# uC.net
KiCad netlist of a schematic drawn in Altium Designer
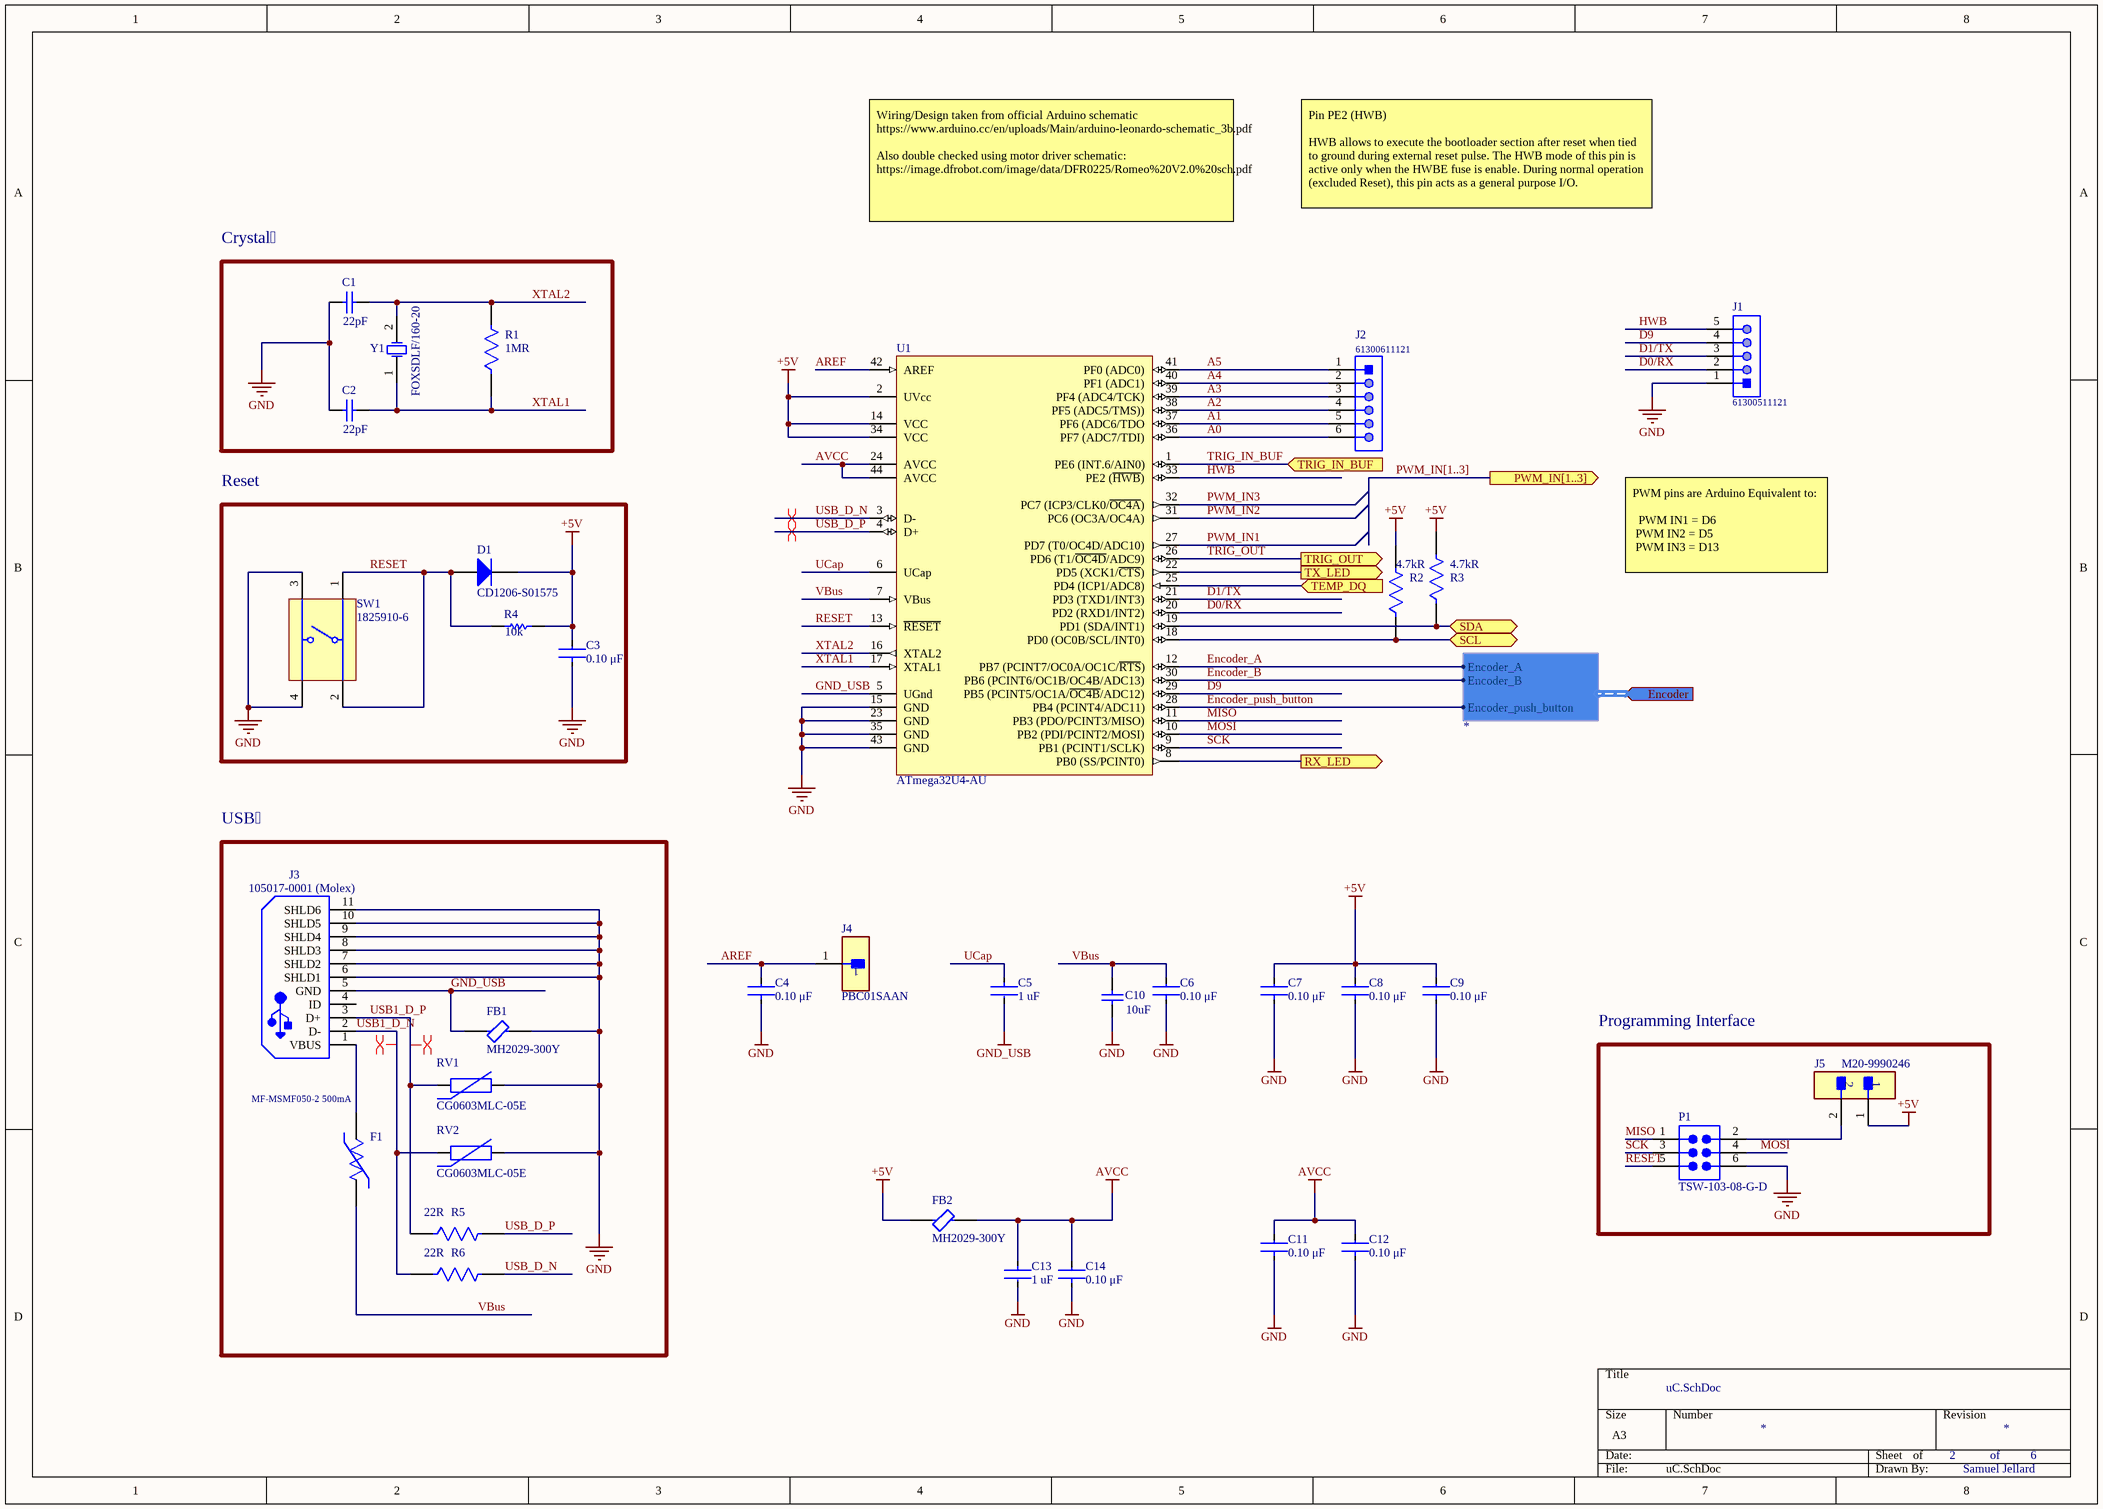
[diagram p0: uC.SchDoc]

(export (version "E")
  (design (tool "Eeschema 10.0.6"))
  (components
    (comp (ref "C1")
      (value "CC0603JRNPO9BN220")
      (footprint "CAPC1608X90X40LL10T20")
      (description "Chip Capacitor, 22 pF, +/- 5%, 50 V, -55 to 125 degC, 0603 (1608 Metric), RoHS, Tape and Reel")
      (libsource (lib "Altium Content Vault") (part "CAP-NP-2"))
    )
    (comp (ref "C2")
      (value "CC0603JRNPO9BN220")
      (footprint "CAPC1608X90X40LL10T20")
      (description "Chip Capacitor, 22 pF, +/- 5%, 50 V, -55 to 125 degC, 0603 (1608 Metric), RoHS, Tape and Reel")
      (libsource (lib "Altium Content Vault") (part "CAP-NP-2"))
    )
    (comp (ref "C3")
      (value "0.10 μF")
      (footprint "FP-C0603C-CF-MFG")
      (description "Multilayer Ceramic Capacitors (MLCC) - SMD/SMT 50volts 0.1uF X7R 10%")
      (fields (field (name "TOLERANCE") "0.1") (field (name "MANUFACTURER") "KEMET"))
      (libsource (lib "Altium Content Vault") (part "b4654b650e69147ec39a6b967a45e02"))
    )
    (comp (ref "C4")
      (value "0.10 μF")
      (footprint "FP-C0603C-CF-MFG")
      (description "Multilayer Ceramic Capacitors (MLCC) - SMD/SMT 50volts 0.1uF X7R 10%")
      (fields (field (name "TOLERANCE") "0.1") (field (name "MANUFACTURER") "KEMET"))
      (libsource (lib "Altium Content Vault") (part "b4654b650e69147ec39a6b967a45e02"))
    )
    (comp (ref "C5")
      (value "1 uF")
      (footprint "FP-CC0603-DA-MFG")
      (description "0603 1 uF 16 V ±10 % Tolerance X7R SMT Multilayer Ceramic Capacitor")
      (fields (field (name "TOLERANCE") "0.1") (field (name "MANUFACTURER") "YAGEO"))
      (libsource (lib "Altium Content Vault") (part "11868f565c42a9108669ba33697ecf6"))
    )
    (comp (ref "C6")
      (value "0.10 μF")
      (footprint "FP-C0603C-CF-MFG")
      (description "Multilayer Ceramic Capacitors (MLCC) - SMD/SMT 50volts 0.1uF X7R 10%")
      (fields (field (name "TOLERANCE") "0.1") (field (name "MANUFACTURER") "KEMET"))
      (libsource (lib "Altium Content Vault") (part "b4654b650e69147ec39a6b967a45e02"))
    )
    (comp (ref "C7")
      (value "0.10 μF")
      (footprint "FP-C0603C-CF-MFG")
      (description "Multilayer Ceramic Capacitors (MLCC) - SMD/SMT 50volts 0.1uF X7R 10%")
      (fields (field (name "TOLERANCE") "0.1") (field (name "MANUFACTURER") "KEMET"))
      (libsource (lib "Altium Content Vault") (part "b4654b650e69147ec39a6b967a45e02"))
    )
    (comp (ref "C8")
      (value "0.10 μF")
      (footprint "FP-C0603C-CF-MFG")
      (description "Multilayer Ceramic Capacitors (MLCC) - SMD/SMT 50volts 0.1uF X7R 10%")
      (fields (field (name "TOLERANCE") "0.1") (field (name "MANUFACTURER") "KEMET"))
      (libsource (lib "Altium Content Vault") (part "b4654b650e69147ec39a6b967a45e02"))
    )
    (comp (ref "C9")
      (value "0.10 μF")
      (footprint "FP-C0603C-CF-MFG")
      (description "Multilayer Ceramic Capacitors (MLCC) - SMD/SMT 50volts 0.1uF X7R 10%")
      (fields (field (name "TOLERANCE") "0.1") (field (name "MANUFACTURER") "KEMET"))
      (libsource (lib "Altium Content Vault") (part "b4654b650e69147ec39a6b967a45e02"))
    )
    (comp (ref "C10")
      (value "10uF")
      (footprint "CAPC0603(1608)100_N")
      (description "CAP 10uF 6.3V ±20% 0603 (1608 Metric) Thickness 1mm SMD")
      (fields (field (name "TOLERANCE") "Â±20%") (field (name "Comment") "C0603C106M9PACTU"))
      (libsource (lib "Altium Content Vault") (part "CAP"))
    )
    (comp (ref "C11")
      (value "0.10 μF")
      (footprint "FP-C0603C-CF-MFG")
      (description "Multilayer Ceramic Capacitors (MLCC) - SMD/SMT 50volts 0.1uF X7R 10%")
      (fields (field (name "TOLERANCE") "0.1") (field (name "MANUFACTURER") "KEMET"))
      (libsource (lib "Altium Content Vault") (part "b4654b650e69147ec39a6b967a45e02"))
    )
    (comp (ref "C12")
      (value "0.10 μF")
      (footprint "FP-C0603C-CF-MFG")
      (description "Multilayer Ceramic Capacitors (MLCC) - SMD/SMT 50volts 0.1uF X7R 10%")
      (fields (field (name "TOLERANCE") "0.1") (field (name "MANUFACTURER") "KEMET"))
      (libsource (lib "Altium Content Vault") (part "b4654b650e69147ec39a6b967a45e02"))
    )
    (comp (ref "C13")
      (value "1 uF")
      (footprint "FP-CC0603-DA-MFG")
      (description "0603 1 uF 16 V ±10 % Tolerance X7R SMT Multilayer Ceramic Capacitor")
      (fields (field (name "TOLERANCE") "0.1") (field (name "MANUFACTURER") "YAGEO"))
      (libsource (lib "Altium Content Vault") (part "11868f565c42a9108669ba33697ecf6"))
    )
    (comp (ref "C14")
      (value "0.10 μF")
      (footprint "FP-C0603C-CF-MFG")
      (description "Multilayer Ceramic Capacitors (MLCC) - SMD/SMT 50volts 0.1uF X7R 10%")
      (fields (field (name "TOLERANCE") "0.1") (field (name "MANUFACTURER") "KEMET"))
      (libsource (lib "Altium Content Vault") (part "b4654b650e69147ec39a6b967a45e02"))
    )
    (comp (ref "D1")
      (value "CD1206-S01575")
      (footprint "BOUR-CD1206-S01575-2_L")
      (description "75 V Small Signal Switching Diode, 150 mA, 2.5 uA, 1026 Molded Package, RoHS, Tape and Reel")
      (fields (field (name "MANUFACTURER") "Bourns"))
      (libsource (lib "Altium Content Vault") (part "BOUR-A1K2-2"))
    )
    (comp (ref "F1")
      (value "MF-MSMF050-2 500mA")
      (footprint "FP-MF-MSMF050-2-MFG")
      (description "PTC RESET FUSE 15V 500MA 1812")
      (fields (field (name "MANUFACTURER") "Bourns") (field (name "MANUFACTURER PART NUMBER") "MF-MSMF050-2"))
      (libsource (lib "Altium Content Vault") (part "fc31388045fc42ab786d6d00b506e9f"))
    )
    (comp (ref "FB1")
      (value "MH2029-300Y")
      (footprint "FP-MH2029-MFG")
      (description "FERRITE BEAD 30 OHM 0805 1LN")
      (fields
        (field (name "OCTOPART") "https://octopart.com/mh2029-300y-bourns-756929")
        (field (name "MANUFACTURER") "Bourns")
      )
      (libsource (lib "Altium Content Vault") (part "5f30dd21d616792df468990f7003faa"))
    )
    (comp (ref "FB2")
      (value "MH2029-300Y")
      (footprint "FP-MH2029-MFG")
      (description "FERRITE BEAD 30 OHM 0805 1LN")
      (fields
        (field (name "OCTOPART") "https://octopart.com/mh2029-300y-bourns-756929")
        (field (name "MANUFACTURER") "Bourns")
      )
      (libsource (lib "Altium Content Vault") (part "5f30dd21d616792df468990f7003faa"))
    )
    (comp (ref "J1")
      (value "61300511121")
      (footprint "61300511121")
      (description "THT Vertical Pin Header WR-PHD, Pitch 2.54 mm, Single Row, 5 pins")
      (fields (field (name "MANUFACTURER") "Wurth Elektronik") (field (name "PUBLISHER") "WurthElektronik"))
      (libsource (lib "Altium Content Vault") (part "WE-CN-1P-M-R5"))
    )
    (comp (ref "J2")
      (value "61300611121")
      (footprint "61300611121")
      (description "THT Vertical Pin Header WR-PHD, Pitch 2.54 mm, Single Row, 6 pins")
      (fields (field (name "MANUFACTURER") "Wurth Elektronik") (field (name "PUBLISHER") "WurthElektronik"))
      (libsource (lib "Altium Content Vault") (part "WE-CN-1P-M-R6"))
    )
    (comp (ref "J3")
      (value "105017-0001 (Molex)")
      (footprint "USB-MICRO-B_V")
      (fields (field (name "MANUFACTURER") "Molex"))
      (libsource (lib "Altium Content Vault") (part "USB-5-6SHLD"))
    )
    (comp (ref "J4")
      (value "PBC01SAAN")
      (footprint "FP-PBC01SAAN-MFG")
      (description "CONN HEADER VERT 1POS")
      (libsource (lib "Altium Content Vault") (part "dd45045ce8184df9e99e12baf3f412c"))
    )
    (comp (ref "J5")
      (value "M20-9990246")
      (footprint "FP-M20-9990246-MFG")
      (description "2.54mm (0.1\") Pitch SIL Vertical PC Tail Pin Header, 6.1mm mating pin height, tin, 2 contacts")
      (fields
        (field (name "OCTOPART") "https://octopart.com/m20-9990246-harwin-2590635")
        (field (name "MANUFACTURER") "Harwin")
      )
      (libsource (lib "Altium Content Vault") (part "3bc925449376181038e59eaffc5286c"))
    )
    (comp (ref "P1")
      (value "TSW-103-08-G-D")
      (footprint "SMTC-TSW-103-08-X-D")
      (description "0.025\" SQ Post Header, Through-hole, Vertical, -55 to 125 degC, 2.54 mm Pitch, 6-Pin, Male, RoHS")
      (fields (field (name "MANUFACTURER") "Samtec"))
      (libsource (lib "Altium Content Vault") (part "SMTC-TSW-103-08-X-D"))
    )
    (comp (ref "R1")
      (value "CRCW06031M00FKEA")
      (footprint "FP-CRCW0603-e3-MFG")
      (description "RES Thick Film, 1MΩ, 1%, 0.1W, 100ppm/°C, 0603")
      (fields (field (name "RESISTANCE") "1MR") (field (name "TOLERANCE") "1%"))
      (libsource (lib "Altium Content Vault") (part "1029c3af85768c4190bb7ad29bc67b5"))
    )
    (comp (ref "R2")
      (value "CRCW06034K70FKEA")
      (footprint "FP-CRCW0603-e3-IPC_A")
      (description "RES Thick Film, 4.7kΩ, 1%, 0.1W, 100ppm/°C, 0603")
      (fields (field (name "RESISTANCE") "4.7kR") (field (name "TOLERANCE") "1%"))
      (libsource (lib "Altium Content Vault") (part "1029c3af85768c4190bb7ad29bc67b5"))
    )
    (comp (ref "R3")
      (value "CRCW06034K70FKEA")
      (footprint "FP-CRCW0603-e3-IPC_A")
      (description "RES Thick Film, 4.7kΩ, 1%, 0.1W, 100ppm/°C, 0603")
      (fields (field (name "RESISTANCE") "4.7kR") (field (name "TOLERANCE") "1%"))
      (libsource (lib "Altium Content Vault") (part "1029c3af85768c4190bb7ad29bc67b5"))
    )
    (comp (ref "R4")
      (value "CRCW060310K0FKEA")
      (footprint "RESC1609X50X30NL8T20")
      (description "Chip Resistor, 10 KOhm, +/- 1%, 100 mW, -55 to 155 degC, 0603 (1608 Metric), RoHS, Tape and Reel")
      (fields (field (name "MANUFACTURER") "Vishay Semiconductor"))
      (libsource (lib "Altium Content Vault") (part "RES-2"))
    )
    (comp (ref "R5")
      (value "CRCW060322R0FKEA")
      (footprint "FP-CRCW0603-e3-IPC_B")
      (description "RES Thick Film, 22Ω, 1%, 0.1W, 100ppm/°C, 0603")
      (fields (field (name "RESISTANCE") "22R") (field (name "TOLERANCE") "1%"))
      (libsource (lib "Altium Content Vault") (part "1029c3af85768c4190bb7ad29bc67b5"))
    )
    (comp (ref "R6")
      (value "CRCW060322R0FKEA")
      (footprint "FP-CRCW0603-e3-IPC_B")
      (description "RES Thick Film, 22Ω, 1%, 0.1W, 100ppm/°C, 0603")
      (fields (field (name "RESISTANCE") "22R") (field (name "TOLERANCE") "1%"))
      (libsource (lib "Altium Content Vault") (part "1029c3af85768c4190bb7ad29bc67b5"))
    )
    (comp (ref "RV1")
      (value "CG0603MLC-05E")
      (footprint "BOUR-CG0603-2_V")
      (description "ESD Protector, 5 V Supply, -40 to 85 degC, 1.6 x 0.8 x 0.55 mm SMD, RoHS, Tape and Reel")
      (fields (field (name "MANUFACTURER") "Bourns"))
      (libsource (lib "Altium Content Vault") (part "BOUR-VSR-2"))
    )
    (comp (ref "RV2")
      (value "CG0603MLC-05E")
      (footprint "BOUR-CG0603-2_V")
      (description "ESD Protector, 5 V Supply, -40 to 85 degC, 1.6 x 0.8 x 0.55 mm SMD, RoHS, Tape and Reel")
      (fields (field (name "MANUFACTURER") "Bourns"))
      (libsource (lib "Altium Content Vault") (part "BOUR-VSR-2"))
    )
    (comp (ref "SW1")
      (value "1825910-6")
      (footprint "TECO-1825910-6_V")
      (description "Tact Switch, SPST-NO, 0.05 A, -35 to 85 degC, 4-Pin THD, RoHS, Bulk")
      (fields (field (name "MANUFACTURER") "TE Connectivity"))
      (libsource (lib "Altium Content Vault") (part "SW-SPST-4_A"))
    )
    (comp (ref "U1")
      (value "ATmega32U4-AU")
      (footprint "44ML_M")
      (libsource (lib "Altium Content Vault") (part "MC-8B-ATM16U4-SQ44"))
    )
    (comp (ref "Y1")
      (value "FOXSDLF/160-20")
      (footprint "FOX-FOXSDLF160-20_V")
      (libsource (lib "Altium Content Vault") (part "XTAL_1-2-2"))
    )
  )
  (nets
    (net (code "2") (name "+5V") (class "Default")
      (node (ref "C3") (pin "2") (pinfunction "2_2") (pintype "passive"))
      (node (ref "C7") (pin "2") (pinfunction "2_2") (pintype "passive"))
      (node (ref "C8") (pin "2") (pinfunction "2_2") (pintype "passive"))
      (node (ref "C9") (pin "2") (pinfunction "2_2") (pintype "passive"))
      (node (ref "D1") (pin "2") (pinfunction "K_2") (pintype "passive"))
      (node (ref "FB2") (pin "2") (pinfunction "2_2") (pintype "passive"))
      (node (ref "J5") (pin "1") (pinfunction "1_1") (pintype "passive"))
      (node (ref "R2") (pin "2") (pinfunction "2_2") (pintype "passive"))
      (node (ref "R3") (pin "2") (pinfunction "2_2") (pintype "passive"))
      (node (ref "R4") (pin "2") (pinfunction "2_2") (pintype "passive"))
      (node (ref "U1") (pin "14") (pinfunction "VCC_14") (pintype "power_in"))
      (node (ref "U1") (pin "2") (pinfunction "UVcc_2") (pintype "power_in"))
      (node (ref "U1") (pin "34") (pinfunction "VCC_34") (pintype "power_in"))
    )
    (net (code "3") (name "/A0") (class "Default")
      (node (ref "J2") (pin "6") (pinfunction "6_6") (pintype "passive"))
      (node (ref "U1") (pin "36") (pinfunction "PF7_(ADC7/TDI)_36") (pintype "bidirectional"))
    )
    (net (code "4") (name "/A1") (class "Default")
      (node (ref "J2") (pin "5") (pinfunction "5_5") (pintype "passive"))
      (node (ref "U1") (pin "37") (pinfunction "PF6_(ADC6/TDO_37") (pintype "bidirectional"))
    )
    (net (code "5") (name "/A2") (class "Default")
      (node (ref "J2") (pin "4") (pinfunction "4_4") (pintype "passive"))
      (node (ref "U1") (pin "38") (pinfunction "PF5_(ADC5/TMS))_38") (pintype "bidirectional"))
    )
    (net (code "6") (name "/A3") (class "Default")
      (node (ref "J2") (pin "3") (pinfunction "3_3") (pintype "passive"))
      (node (ref "U1") (pin "39") (pinfunction "PF4_(ADC4/TCK)_39") (pintype "bidirectional"))
    )
    (net (code "7") (name "/A4") (class "Default")
      (node (ref "J2") (pin "2") (pinfunction "2_2") (pintype "passive"))
      (node (ref "U1") (pin "40") (pinfunction "PF1_(ADC1)_40") (pintype "bidirectional"))
    )
    (net (code "8") (name "/A5") (class "Default")
      (node (ref "J2") (pin "1") (pinfunction "1_1") (pintype "passive"))
      (node (ref "U1") (pin "41") (pinfunction "PF0_(ADC0)_41") (pintype "bidirectional"))
    )
    (net (code "9") (name "/AREF") (class "Default")
      (node (ref "C4") (pin "2") (pinfunction "2_2") (pintype "passive"))
      (node (ref "J4") (pin "1") (pinfunction "1_1") (pintype "passive"))
      (node (ref "U1") (pin "42") (pinfunction "AREF_42") (pintype "input"))
    )
    (net (code "10") (name "/D0{slash}RX") (class "Default")
      (node (ref "J1") (pin "2") (pinfunction "2_2") (pintype "passive"))
      (node (ref "U1") (pin "20") (pinfunction "PD2_(RXD1/INT2)_20") (pintype "bidirectional"))
    )
    (net (code "11") (name "/D1{slash}TX") (class "Default")
      (node (ref "J1") (pin "3") (pinfunction "3_3") (pintype "passive"))
      (node (ref "U1") (pin "21") (pinfunction "PD3_(TXD1/INT3)_21") (pintype "bidirectional"))
    )
    (net (code "12") (name "/D9") (class "Default")
      (node (ref "J1") (pin "4") (pinfunction "4_4") (pintype "passive"))
      (node (ref "U1") (pin "29") (pinfunction "PB5_(PCINT5/OC1A/~{OC4B}/ADC12)_29") (pintype "bidirectional"))
    )
    (net (code "13") (name "/Encoder_A") (class "Default")
      (node (ref "U1") (pin "12") (pinfunction "PB7_(PCINT7/OC0A/OC1C/~{RTS})_12") (pintype "bidirectional"))
    )
    (net (code "14") (name "/Encoder_B") (class "Default")
      (node (ref "U1") (pin "30") (pinfunction "PB6_(PCINT6/OC1B/OC4B/ADC13)_30") (pintype "bidirectional"))
    )
    (net (code "15") (name "/Encoder_push_button") (class "Default")
      (node (ref "U1") (pin "28") (pinfunction "PB4_(PCINT4/ADC11)_28") (pintype "bidirectional"))
    )
    (net (code "16") (name "/HWB") (class "Default")
      (node (ref "J1") (pin "5") (pinfunction "5_5") (pintype "passive"))
      (node (ref "U1") (pin "33") (pinfunction "PE2_(~{HWB})_33") (pintype "bidirectional"))
    )
    (net (code "17") (name "/MISO") (class "Default")
      (node (ref "P1") (pin "1") (pinfunction "1_1") (pintype "passive"))
      (node (ref "U1") (pin "11") (pinfunction "PB3_(PDO/PCINT3/MISO)_11") (pintype "bidirectional"))
    )
    (net (code "18") (name "/MOSI") (class "Default")
      (node (ref "P1") (pin "4") (pinfunction "4_4") (pintype "passive"))
      (node (ref "U1") (pin "10") (pinfunction "PB2_(PDI/PCINT2/MOSI)_10") (pintype "bidirectional"))
    )
    (net (code "19") (name "/PWM_IN1") (class "Default")
      (node (ref "U1") (pin "27") (pinfunction "PD7_(T0/OC4D/ADC10)_27") (pintype "output"))
    )
    (net (code "20") (name "/PWM_IN2") (class "Default")
      (node (ref "U1") (pin "31") (pinfunction "PC6_(OC3A/OC4A)_31") (pintype "output"))
    )
    (net (code "21") (name "/PWM_IN3") (class "Default")
      (node (ref "U1") (pin "32") (pinfunction "PC7_(ICP3/CLK0/~{OC4A})_32") (pintype "output"))
    )
    (net (code "23") (name "/RESET") (class "Default")
      (node (ref "D1") (pin "1") (pinfunction "A_1") (pintype "passive"))
      (node (ref "P1") (pin "5") (pinfunction "5_5") (pintype "passive"))
      (node (ref "R4") (pin "1") (pinfunction "1_1") (pintype "passive"))
      (node (ref "SW1") (pin "1") (pinfunction "1_1") (pintype "passive"))
      (node (ref "SW1") (pin "2") (pinfunction "2_2") (pintype "passive"))
      (node (ref "U1") (pin "13") (pinfunction "~{RESET}_13") (pintype "input"))
    )
    (net (code "24") (name "/RX_LED") (class "Default")
      (node (ref "U1") (pin "8") (pinfunction "PB0_(SS/PCINT0)_8") (pintype "output"))
    )
    (net (code "25") (name "/SCK") (class "Default")
      (node (ref "P1") (pin "3") (pinfunction "3_3") (pintype "passive"))
      (node (ref "U1") (pin "9") (pinfunction "PB1_(PCINT1/SCLK)_9") (pintype "bidirectional"))
    )
    (net (code "26") (name "/SCL") (class "Default")
      (node (ref "R2") (pin "1") (pinfunction "1_1") (pintype "passive"))
      (node (ref "U1") (pin "18") (pinfunction "PD0_(OC0B/SCL/INT0)_18") (pintype "bidirectional"))
    )
    (net (code "27") (name "/SDA") (class "Default")
      (node (ref "R3") (pin "1") (pinfunction "1_1") (pintype "passive"))
      (node (ref "U1") (pin "19") (pinfunction "PD1_(SDA/INT1)_19") (pintype "bidirectional"))
    )
    (net (code "28") (name "/TEMP_DQ") (class "Default")
      (node (ref "U1") (pin "25") (pinfunction "PD4_(ICP1/ADC8)_25") (pintype "input"))
    )
    (net (code "29") (name "/TRIG_IN_BUF") (class "Default")
      (node (ref "U1") (pin "1") (pinfunction "PE6_(INT.6/AIN0)_1") (pintype "bidirectional"))
    )
    (net (code "30") (name "/TRIG_OUT") (class "Default")
      (node (ref "U1") (pin "26") (pinfunction "PD6_(T1/~{OC4D}/ADC9)_26") (pintype "bidirectional"))
    )
    (net (code "31") (name "/TX_LED") (class "Default")
      (node (ref "U1") (pin "22") (pinfunction "PD5_(XCK1/~{CTS})_22") (pintype "output"))
    )
    (net (code "32") (name "/UCap") (class "Default")
      (node (ref "C5") (pin "1") (pinfunction "1_1") (pintype "passive"))
      (node (ref "U1") (pin "6") (pinfunction "UCap_6") (pintype "passive"))
    )
    (net (code "33") (name "/USB1_D_N") (class "Default")
      (node (ref "J3") (pin "2") (pinfunction "D-_2") (pintype "passive"))
      (node (ref "R6") (pin "1") (pinfunction "1_1") (pintype "passive"))
      (node (ref "RV2") (pin "1") (pinfunction "1_1") (pintype "passive"))
    )
    (net (code "34") (name "/USB1_D_P") (class "Default")
      (node (ref "J3") (pin "3") (pinfunction "D+_3") (pintype "passive"))
      (node (ref "R5") (pin "1") (pinfunction "1_1") (pintype "passive"))
      (node (ref "RV1") (pin "1") (pinfunction "1_1") (pintype "passive"))
    )
    (net (code "35") (name "/USB_D_N") (class "Default")
      (node (ref "R6") (pin "2") (pinfunction "2_2") (pintype "passive"))
      (node (ref "U1") (pin "3") (pinfunction "D-_3") (pintype "bidirectional"))
    )
    (net (code "36") (name "/USB_D_P") (class "Default")
      (node (ref "R5") (pin "2") (pinfunction "2_2") (pintype "passive"))
      (node (ref "U1") (pin "4") (pinfunction "D+_4") (pintype "bidirectional"))
    )
    (net (code "37") (name "/VBus") (class "Default")
      (node (ref "C10") (pin "2") (pinfunction "2_2") (pintype "passive"))
      (node (ref "C6") (pin "2") (pinfunction "2_2") (pintype "passive"))
      (node (ref "F1") (pin "2") (pinfunction "2_2") (pintype "passive"))
      (node (ref "U1") (pin "7") (pinfunction "VBus_7") (pintype "input"))
    )
    (net (code "38") (name "/XTAL1") (class "Default")
      (node (ref "C2") (pin "2") (pinfunction "2_2") (pintype "passive"))
      (node (ref "R1") (pin "1") (pinfunction "1_1") (pintype "passive"))
      (node (ref "U1") (pin "17") (pinfunction "XTAL1_17") (pintype "input"))
      (node (ref "Y1") (pin "1") (pinfunction "X1_1") (pintype "passive"))
    )
    (net (code "39") (name "/XTAL2") (class "Default")
      (node (ref "C1") (pin "2") (pinfunction "2_2") (pintype "passive"))
      (node (ref "R1") (pin "2") (pinfunction "2_2") (pintype "passive"))
      (node (ref "U1") (pin "16") (pinfunction "XTAL2_16") (pintype "output"))
      (node (ref "Y1") (pin "2") (pinfunction "X2_2") (pintype "passive"))
    )
    (net (code "41") (name "AVCC") (class "Default")
      (node (ref "C11") (pin "2") (pinfunction "2_2") (pintype "passive"))
      (node (ref "C12") (pin "2") (pinfunction "2_2") (pintype "passive"))
      (node (ref "C13") (pin "1") (pinfunction "1_1") (pintype "passive"))
      (node (ref "C14") (pin "2") (pinfunction "2_2") (pintype "passive"))
      (node (ref "FB2") (pin "1") (pinfunction "1_1") (pintype "passive"))
      (node (ref "U1") (pin "24") (pinfunction "AVCC_24") (pintype "power_in"))
      (node (ref "U1") (pin "44") (pinfunction "AVCC_44") (pintype "power_in"))
    )
    (net (code "42") (name "GND") (class "Default")
      (node (ref "C1") (pin "1") (pinfunction "1_1") (pintype "passive"))
      (node (ref "C10") (pin "1") (pinfunction "1_1") (pintype "passive"))
      (node (ref "C11") (pin "1") (pinfunction "1_1") (pintype "passive"))
      (node (ref "C12") (pin "1") (pinfunction "1_1") (pintype "passive"))
      (node (ref "C13") (pin "2") (pinfunction "2_2") (pintype "passive"))
      (node (ref "C14") (pin "1") (pinfunction "1_1") (pintype "passive"))
      (node (ref "C2") (pin "1") (pinfunction "1_1") (pintype "passive"))
      (node (ref "C3") (pin "1") (pinfunction "1_1") (pintype "passive"))
      (node (ref "C4") (pin "1") (pinfunction "1_1") (pintype "passive"))
      (node (ref "C6") (pin "1") (pinfunction "1_1") (pintype "passive"))
      (node (ref "C7") (pin "1") (pinfunction "1_1") (pintype "passive"))
      (node (ref "C8") (pin "1") (pinfunction "1_1") (pintype "passive"))
      (node (ref "C9") (pin "1") (pinfunction "1_1") (pintype "passive"))
      (node (ref "FB1") (pin "2") (pinfunction "2_2") (pintype "passive"))
      (node (ref "J1") (pin "1") (pinfunction "1_1") (pintype "passive"))
      (node (ref "J3") (pin "10") (pinfunction "SHLD5_10") (pintype "passive"))
      (node (ref "J3") (pin "11") (pinfunction "SHLD6_11") (pintype "passive"))
      (node (ref "J3") (pin "6") (pinfunction "SHLD1_6") (pintype "passive"))
      (node (ref "J3") (pin "7") (pinfunction "SHLD2_7") (pintype "passive"))
      (node (ref "J3") (pin "8") (pinfunction "SHLD3_8") (pintype "passive"))
      (node (ref "J3") (pin "9") (pinfunction "SHLD4_9") (pintype "passive"))
      (node (ref "P1") (pin "6") (pinfunction "6_6") (pintype "passive"))
      (node (ref "RV1") (pin "2") (pinfunction "2_2") (pintype "passive"))
      (node (ref "RV2") (pin "2") (pinfunction "2_2") (pintype "passive"))
      (node (ref "SW1") (pin "3") (pinfunction "3_3") (pintype "passive"))
      (node (ref "SW1") (pin "4") (pinfunction "4_4") (pintype "passive"))
      (node (ref "U1") (pin "15") (pinfunction "GND_15") (pintype "power_in"))
      (node (ref "U1") (pin "23") (pinfunction "GND_23") (pintype "power_in"))
      (node (ref "U1") (pin "35") (pinfunction "GND_35") (pintype "power_in"))
      (node (ref "U1") (pin "43") (pinfunction "GND_43") (pintype "power_in"))
    )
    (net (code "43") (name "GND_USB") (class "Default")
      (node (ref "C5") (pin "2") (pinfunction "2_2") (pintype "passive"))
      (node (ref "FB1") (pin "1") (pinfunction "1_1") (pintype "passive"))
      (node (ref "J3") (pin "5") (pinfunction "GND_5") (pintype "passive"))
      (node (ref "U1") (pin "5") (pinfunction "UGnd_5") (pintype "power_in"))
    )
    (net (code "44") (name "Net-(J3-VBUS)") (class "Default")
      (node (ref "F1") (pin "1") (pinfunction "1_1") (pintype "passive"))
      (node (ref "J3") (pin "1") (pinfunction "VBUS_1") (pintype "passive"))
    )
    (net (code "45") (name "Net-(J5-Pad2)") (class "Default")
      (node (ref "J5") (pin "2") (pinfunction "2_2") (pintype "passive"))
      (node (ref "P1") (pin "2") (pinfunction "2_2") (pintype "passive"))
    )
    (net (code "46") (name "unconnected-(J3-ID-Pad4)") (class "Default")
      (node (ref "J3") (pin "4") (pinfunction "ID_4") (pintype "passive"))
    )
  )
)
